# Sheet1.net
KiCad netlist of a schematic drawn in Altium Designer
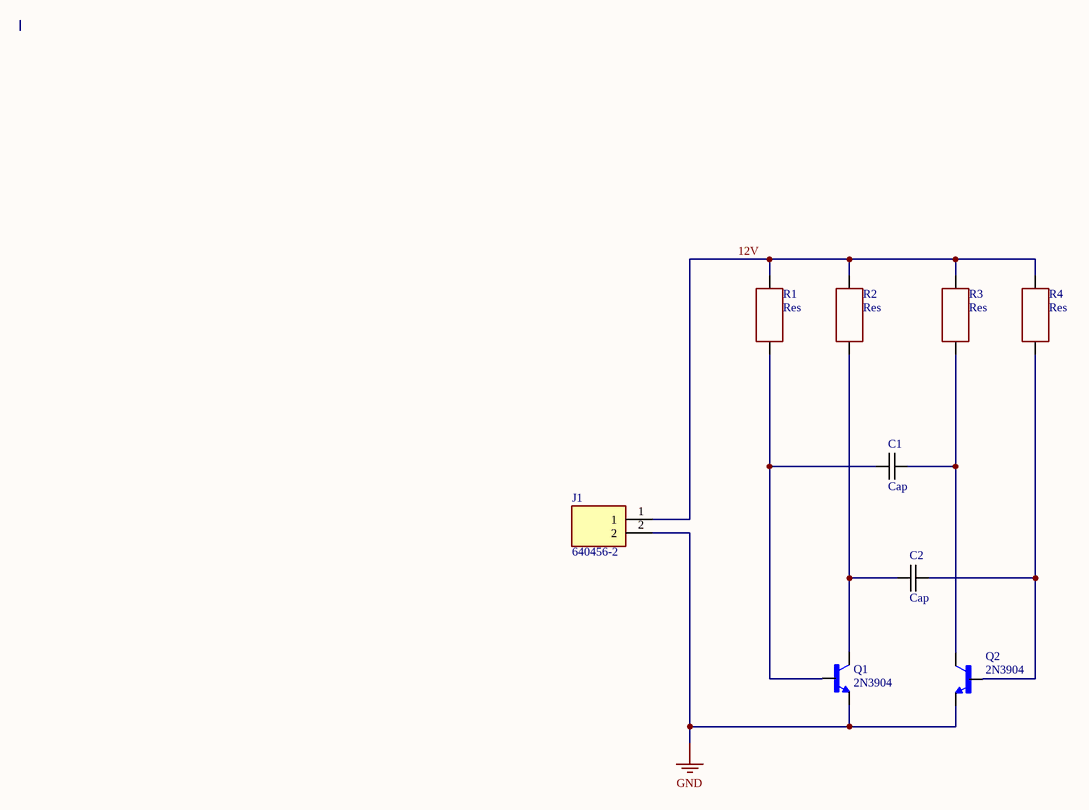
[diagram p0: Sheet1.SchDoc]

(export (version "E")
  (design (tool "Eeschema 10.0.6"))
  (components
    (comp (ref "C1") (value "Cap") (footprint "Cap") (libsource (lib "Capacitor") (part "Cap")))
    (comp (ref "C2") (value "Cap") (footprint "Cap") (libsource (lib "Capacitor") (part "Cap")))
    (comp (ref "J1")
      (value "640456-2")
      (footprint "TE_640456-2")
      (description "Header Friction Lock MTA-100 2 250 VAC Polyester Tin Copper Alloy Tin ¦ TE Connectivity 640456-2")
      (fields (field (name "MF") "TE Connectivity"))
      (libsource (lib "header") (part "640456-2"))
    )
    (comp (ref "Q1")
      (value "2N3904")
      (footprint "TO92254P460H750-3")
      (description "BJT, TO-92, 40V, 200mA, NPN, 0.625W, 150Â°C")
      (fields (field (name "MF") "Diotec Semiconductor"))
      (libsource (lib "2N3904") (part "2N3904"))
    )
    (comp (ref "Q2")
      (value "2N3904")
      (footprint "TO92254P460H750-3")
      (description "BJT, TO-92, 40V, 200mA, NPN, 0.625W, 150Â°C")
      (fields (field (name "MF") "Diotec Semiconductor"))
      (libsource (lib "") (part "2N3904_1"))
    )
    (comp (ref "R1") (value "Res") (footprint "Res 1") (libsource (lib "Res") (part "Res")))
    (comp (ref "R2") (value "Res") (footprint "Res 1") (libsource (lib "Res") (part "Res")))
    (comp (ref "R3") (value "Res") (footprint "Res 1") (libsource (lib "Res") (part "Res")))
    (comp (ref "R4") (value "Res") (footprint "Res 1") (libsource (lib "Res") (part "Res")))
  )
  (nets
    (net (code "1") (name "/12V") (class "Default")
      (node (ref "J1") (pin "1") (pinfunction "1_1") (pintype "passive"))
      (node (ref "R1") (pin "2") (pinfunction "2_2") (pintype "passive"))
      (node (ref "R2") (pin "2") (pinfunction "2_2") (pintype "passive"))
      (node (ref "R3") (pin "2") (pinfunction "2_2") (pintype "passive"))
      (node (ref "R4") (pin "2") (pinfunction "2_2") (pintype "passive"))
    )
    (net (code "2") (name "GND") (class "Default")
      (node (ref "J1") (pin "2") (pinfunction "2_2") (pintype "passive"))
      (node (ref "Q1") (pin "1") (pinfunction "E_1") (pintype "passive"))
      (node (ref "Q2") (pin "1") (pinfunction "E_1") (pintype "passive"))
    )
    (net (code "3") (name "Net-(Q1-B)") (class "Default")
      (node (ref "C1") (pin "1") (pinfunction "1_1") (pintype "passive"))
      (node (ref "Q1") (pin "2") (pinfunction "B_2") (pintype "passive"))
      (node (ref "R1") (pin "1") (pinfunction "1_1") (pintype "passive"))
    )
    (net (code "4") (name "Net-(Q1-C)") (class "Default")
      (node (ref "C2") (pin "1") (pinfunction "1_1") (pintype "passive"))
      (node (ref "Q1") (pin "3") (pinfunction "C_3") (pintype "passive"))
      (node (ref "R2") (pin "1") (pinfunction "1_1") (pintype "passive"))
    )
    (net (code "5") (name "Net-(Q2-B)") (class "Default")
      (node (ref "C2") (pin "2") (pinfunction "2_2") (pintype "passive"))
      (node (ref "Q2") (pin "2") (pinfunction "B_2") (pintype "passive"))
      (node (ref "R4") (pin "1") (pinfunction "1_1") (pintype "passive"))
    )
    (net (code "6") (name "Net-(Q2-C)") (class "Default")
      (node (ref "C1") (pin "2") (pinfunction "2_2") (pintype "passive"))
      (node (ref "Q2") (pin "3") (pinfunction "C_3") (pintype "passive"))
      (node (ref "R3") (pin "1") (pinfunction "1_1") (pintype "passive"))
    )
  )
)
